# MCU_ZC-ST4X-A005A_1.net
KiCad netlist of a schematic drawn in Altium Designer
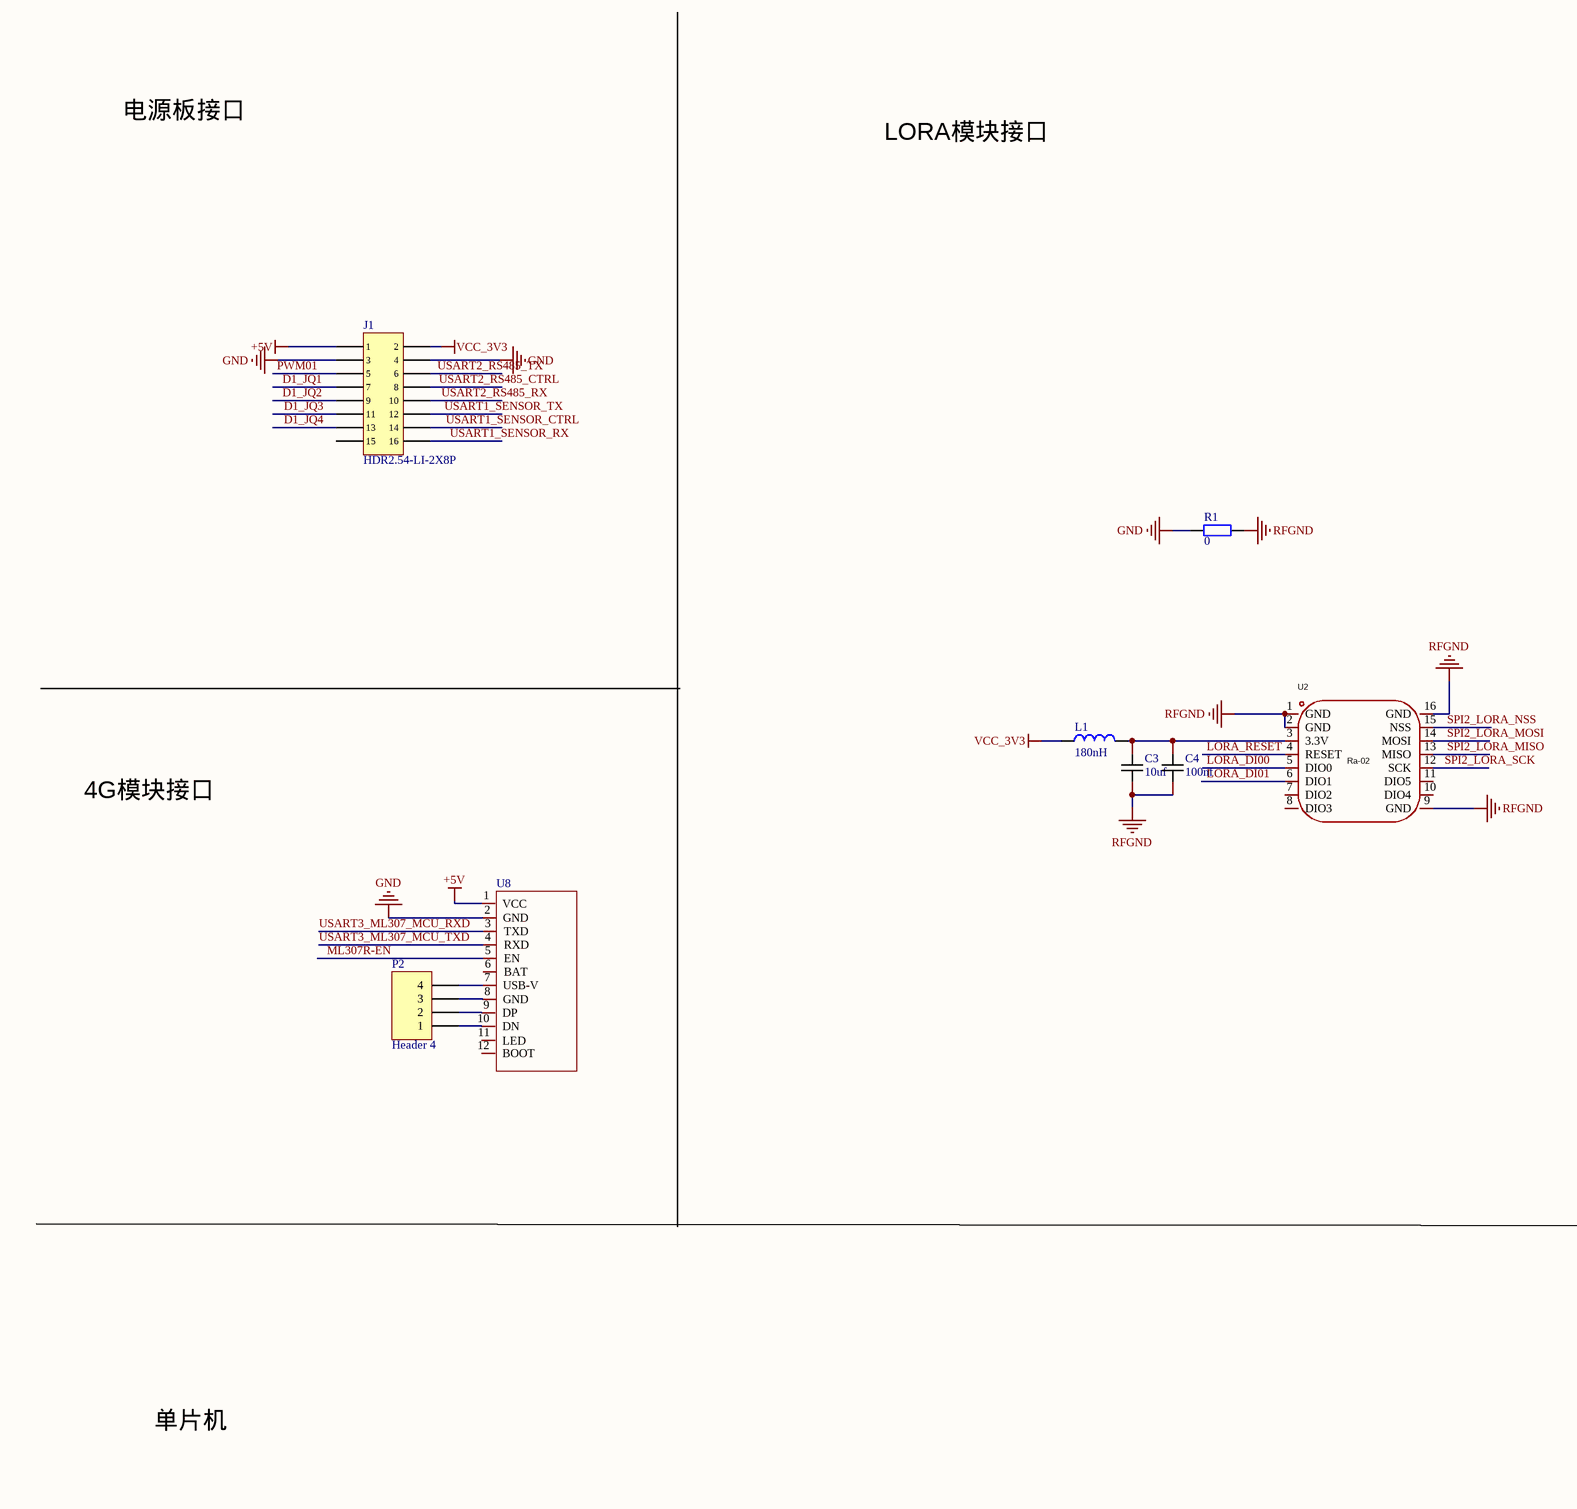
[diagram p0: MCU(ZC-ST4X-A005A)(1).SchDoc, top left]
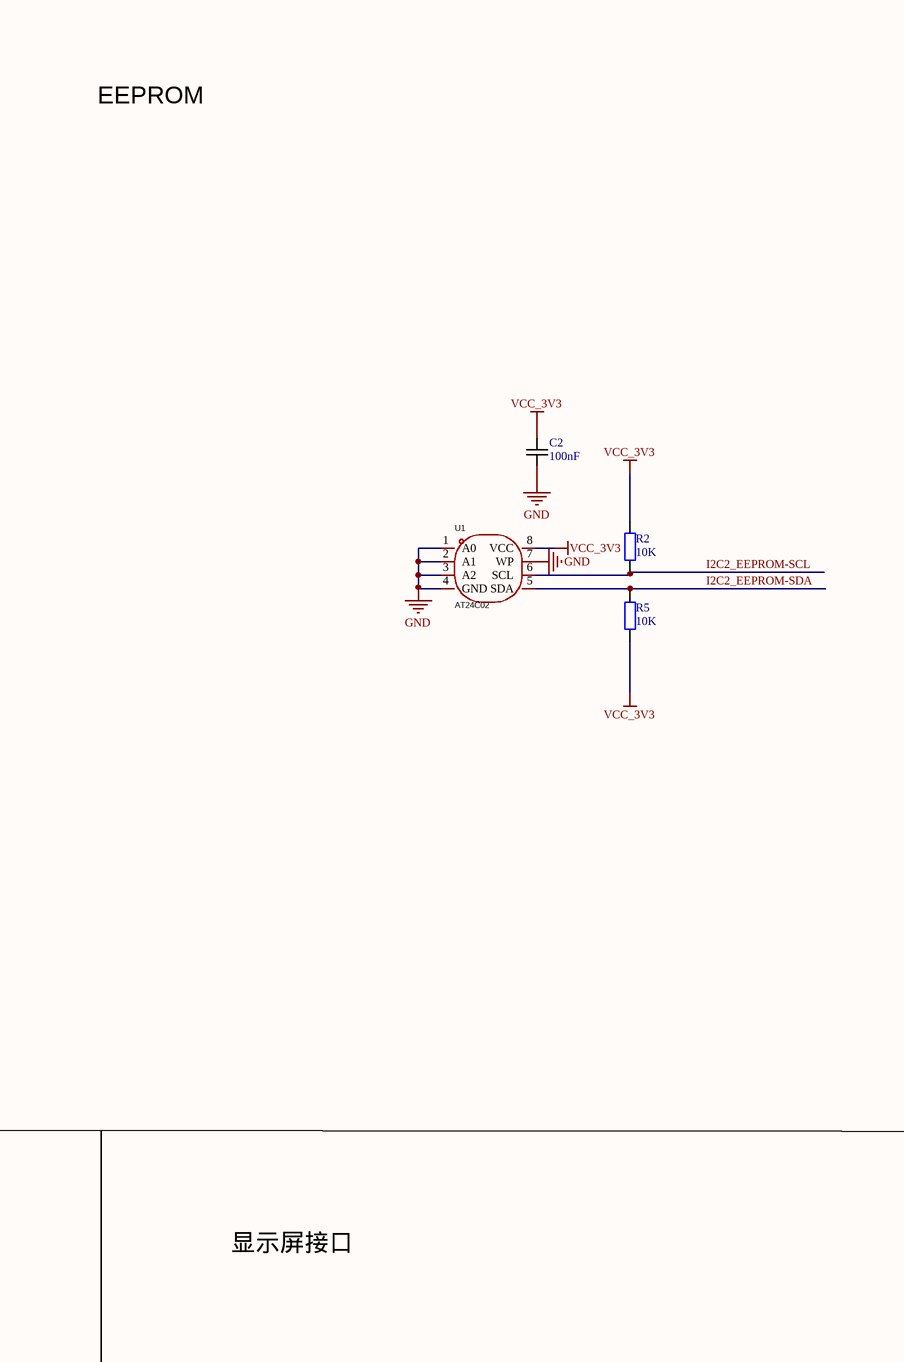
[diagram p1: MCU(ZC-ST4X-A005A)(1).SchDoc, top middle]
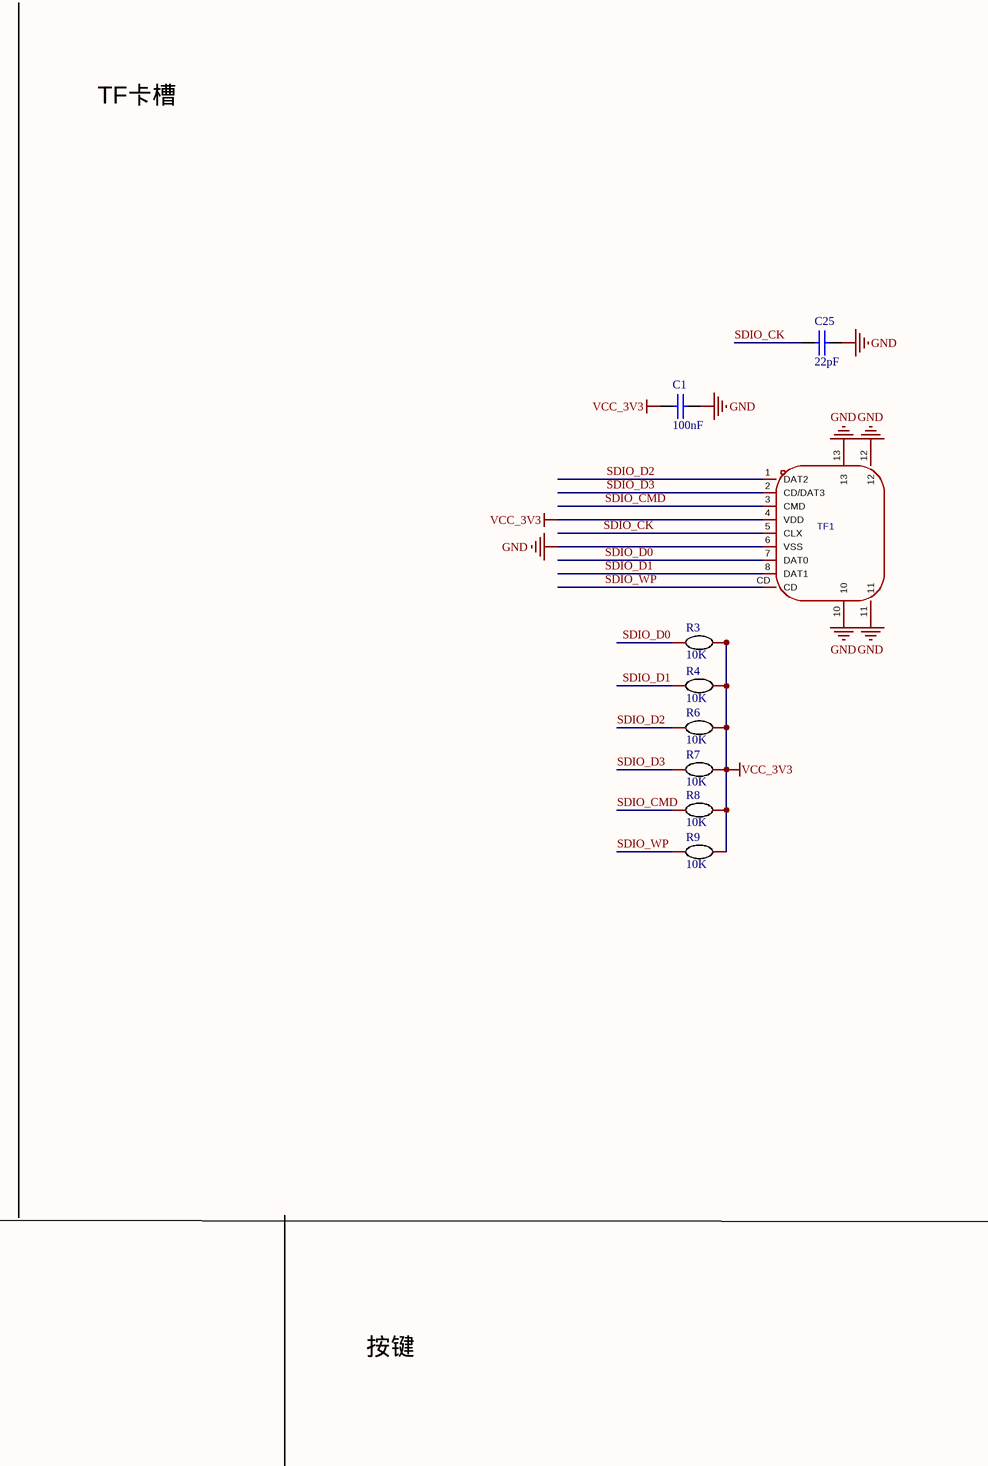
[diagram p2: MCU(ZC-ST4X-A005A)(1).SchDoc, top right]
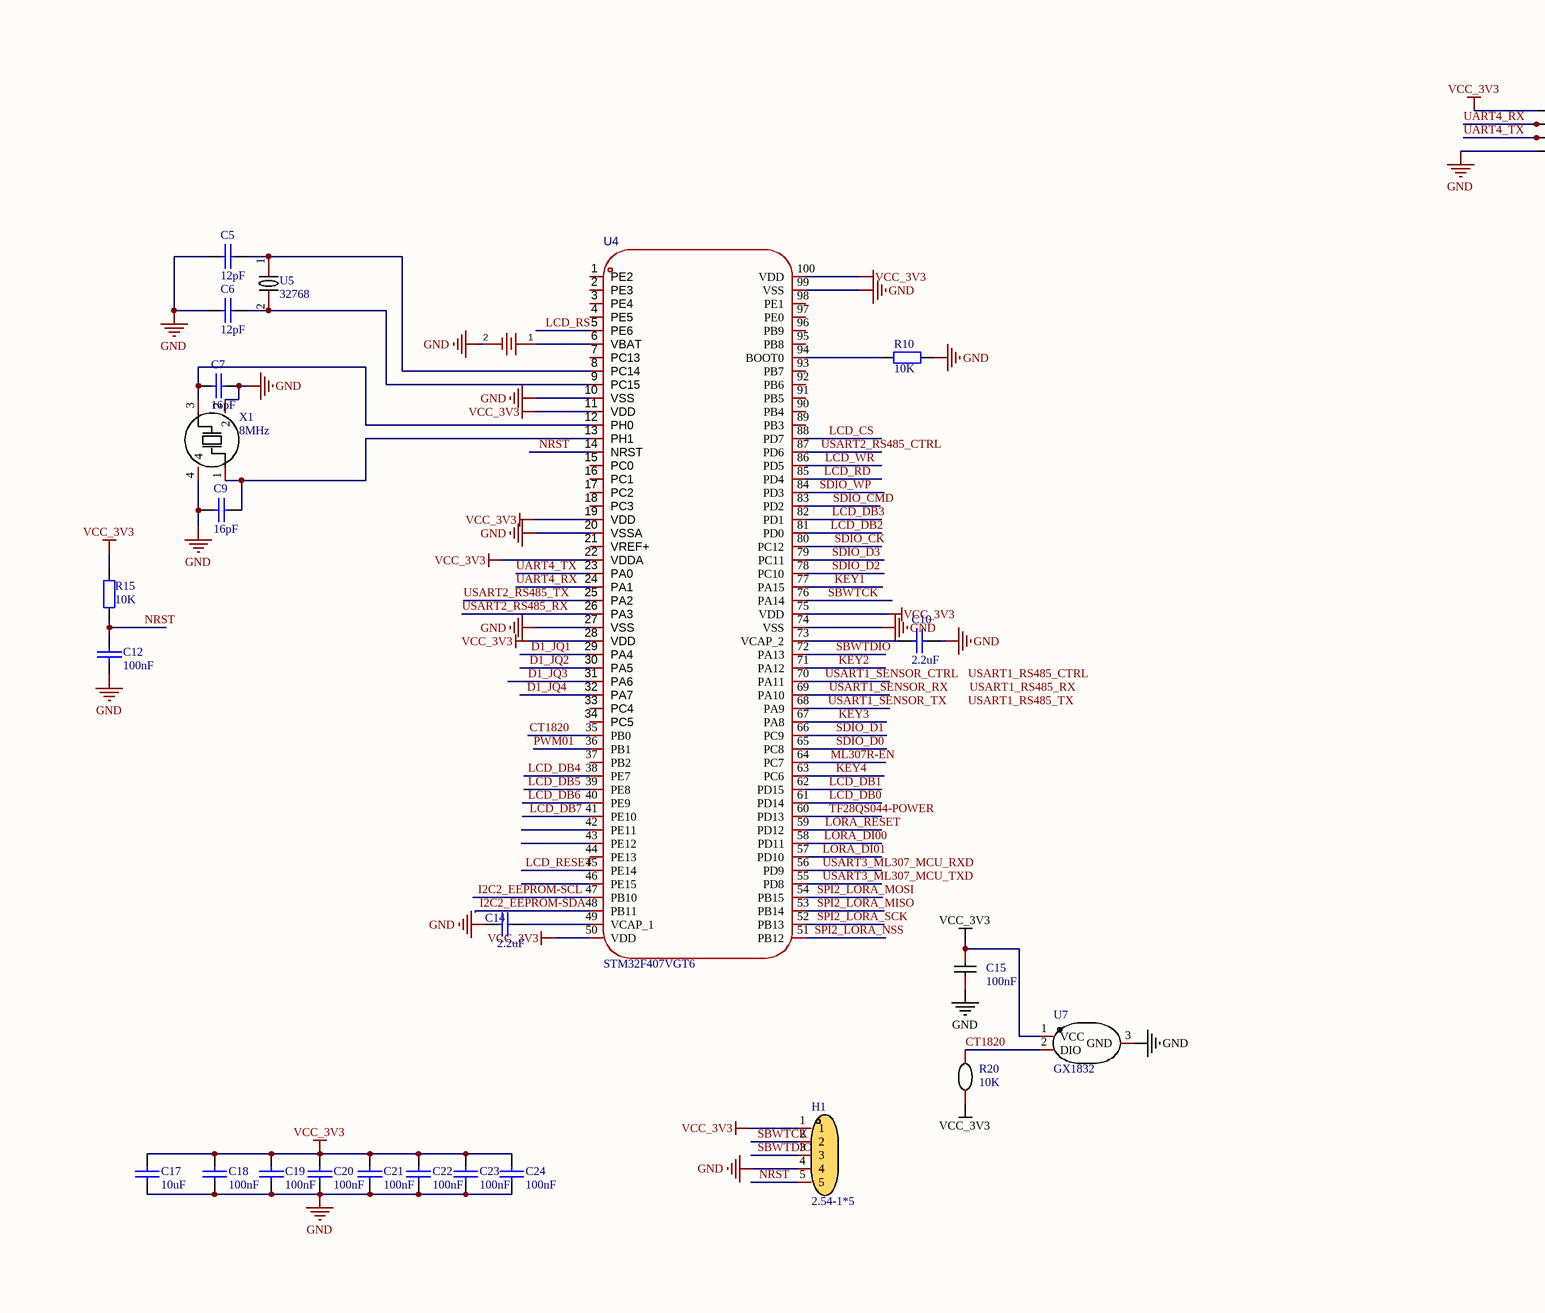
[diagram p3: MCU(ZC-ST4X-A005A)(1).SchDoc, bottom left]
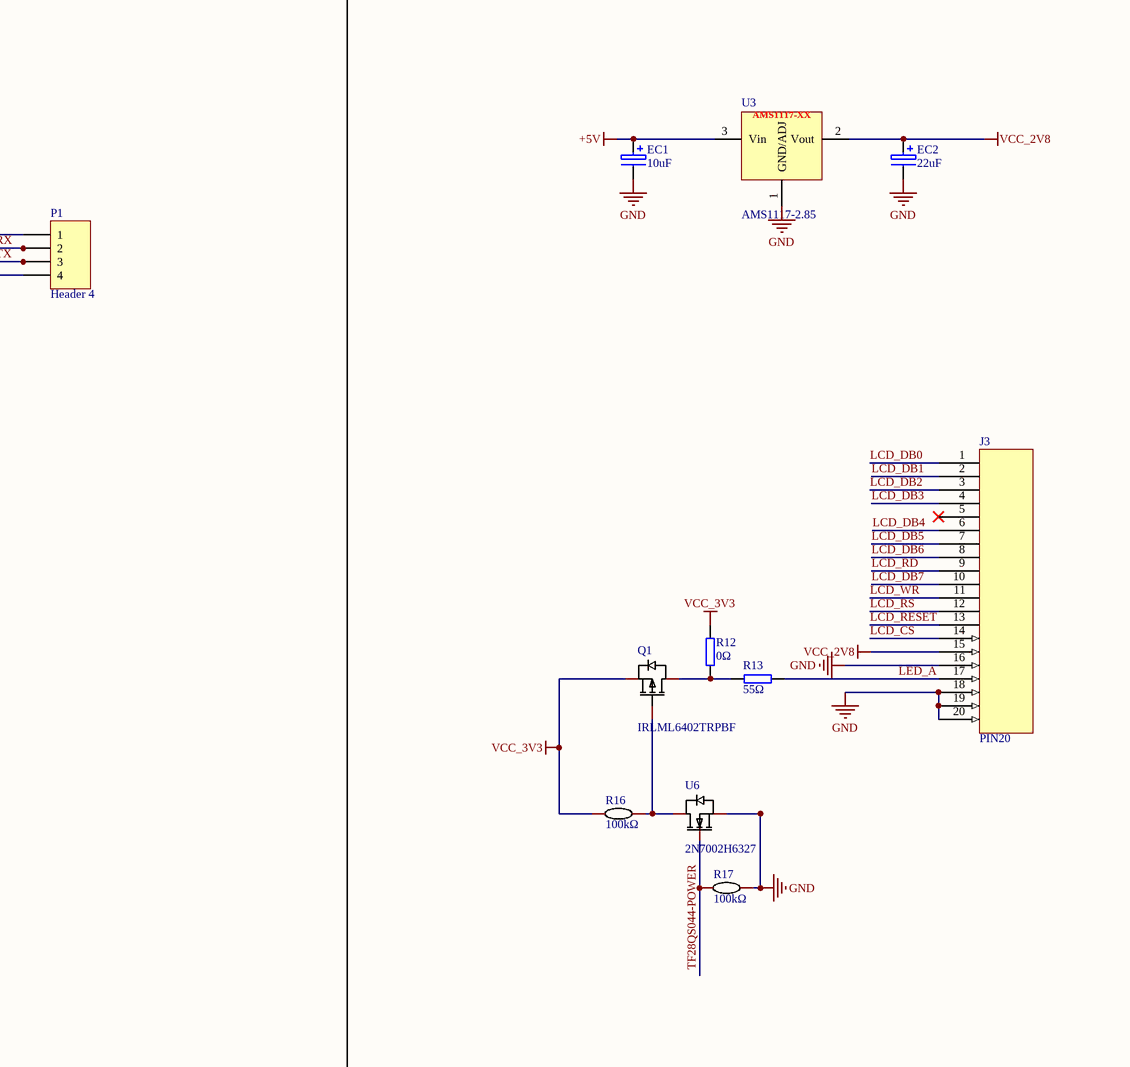
[diagram p4: MCU(ZC-ST4X-A005A)(1).SchDoc, bottom middle]
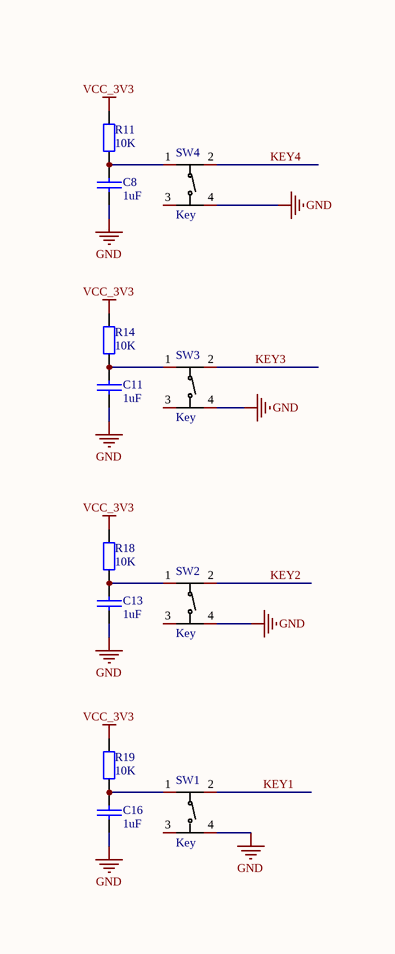
[diagram p5: MCU(ZC-ST4X-A005A)(1).SchDoc, bottom right]

(export (version "E")
  (design (tool "Eeschema 10.0.6"))
  (components
    (comp (ref "BAT1")
      (value "KH-CR2032-2-1")
      (footprint "BAT-TH_CR2032-BS-6-1")
      (libsource (lib "altium-import") (part "root_0_KH-CR2032-2-1_"))
    )
    (comp (ref "C1")
      (value "100nF")
      (footprint "C-0603")
      (description "电容")
      (libsource (lib "泰开常用器件") (part "C普通电容"))
    )
    (comp (ref "C2")
      (value "100nF")
      (footprint "C-0603")
      (fields
        (field (name "MANUFACTURER") "FH(风华)")
        (field (name "MANUFACTURER PART") "0805B104K500NT")
        (field (name "TOLERANCE") "±10%")
      )
      (libsource (lib "") (part "root_1_0805B104K500NT__1"))
    )
    (comp (ref "C3")
      (value "10uf")
      (footprint "C-0603")
      (fields
        (field (name "MANUFACTURER") "FH(风华)")
        (field (name "MANUFACTURER PART") "0805B104K500NT")
        (field (name "TOLERANCE") "±10%")
      )
      (libsource (lib "") (part "root_1_0805B104K500NT__1"))
    )
    (comp (ref "C4")
      (value "100nf")
      (footprint "C-0603")
      (fields
        (field (name "MANUFACTURER") "FH(风华)")
        (field (name "MANUFACTURER PART") "0805B104K500NT")
        (field (name "TOLERANCE") "±10%")
      )
      (libsource (lib "") (part "root_1_0805B104K500NT__1"))
    )
    (comp (ref "C5")
      (value "12pF")
      (footprint "C-0603")
      (description "电容")
      (libsource (lib "泰开常用器件") (part "C普通电容"))
    )
    (comp (ref "C6")
      (value "12pF")
      (footprint "C-0603")
      (description "电容")
      (libsource (lib "泰开常用器件") (part "C普通电容"))
    )
    (comp (ref "C7")
      (value "16pF")
      (footprint "C-0603")
      (description "电容")
      (libsource (lib "泰开常用器件") (part "C普通电容"))
    )
    (comp (ref "C8")
      (value "1uF")
      (footprint "C-0805")
      (description "电容")
      (libsource (lib "泰开常用器件") (part "C普通电容"))
    )
    (comp (ref "C9")
      (value "16pF")
      (footprint "C-0603")
      (description "电容")
      (libsource (lib "泰开常用器件") (part "C普通电容"))
    )
    (comp (ref "C10")
      (value "2.2uF")
      (footprint "C-0603")
      (description "电容")
      (libsource (lib "泰开常用器件") (part "C普通电容"))
    )
    (comp (ref "C11")
      (value "1uF")
      (footprint "C-0805")
      (description "电容")
      (libsource (lib "泰开常用器件") (part "C普通电容"))
    )
    (comp (ref "C12")
      (value "100nF")
      (footprint "C-0603")
      (description "电容")
      (libsource (lib "泰开常用器件") (part "C普通电容"))
    )
    (comp (ref "C13")
      (value "1uF")
      (footprint "C-0805")
      (description "电容")
      (libsource (lib "泰开常用器件") (part "C普通电容"))
    )
    (comp (ref "C14")
      (value "2.2uF")
      (footprint "C-0603")
      (description "电容")
      (libsource (lib "泰开常用器件") (part "C普通电容"))
    )
    (comp (ref "C15")
      (value "100nF")
      (footprint "C-0603")
      (fields
        (field (name "NAME") "100nF")
        (field (name "MANUFACTURER") "FH(风华)")
        (field (name "MANUFACTURER PART") "0805B104K500NT")
        (field (name "TOLERANCE") "±10%")
      )
      (libsource (lib "altium-import") (part "root_1_0805B104K500NT_"))
    )
    (comp (ref "C16")
      (value "1uF")
      (footprint "C-0805")
      (description "电容")
      (libsource (lib "泰开常用器件") (part "C普通电容"))
    )
    (comp (ref "C17")
      (value "10uF")
      (footprint "C-0603")
      (description "电容")
      (libsource (lib "泰开常用器件") (part "C普通电容"))
    )
    (comp (ref "C18")
      (value "100nF")
      (footprint "C-0603")
      (description "电容")
      (libsource (lib "泰开常用器件") (part "C普通电容"))
    )
    (comp (ref "C19")
      (value "100nF")
      (footprint "C-0603")
      (description "电容")
      (libsource (lib "泰开常用器件") (part "C普通电容"))
    )
    (comp (ref "C20")
      (value "100nF")
      (footprint "C-0603")
      (description "电容")
      (libsource (lib "泰开常用器件") (part "C普通电容"))
    )
    (comp (ref "C21")
      (value "100nF")
      (footprint "C-0603")
      (description "电容")
      (libsource (lib "泰开常用器件") (part "C普通电容"))
    )
    (comp (ref "C22")
      (value "100nF")
      (footprint "C-0603")
      (description "电容")
      (libsource (lib "泰开常用器件") (part "C普通电容"))
    )
    (comp (ref "C23")
      (value "100nF")
      (footprint "C-0603")
      (description "电容")
      (libsource (lib "泰开常用器件") (part "C普通电容"))
    )
    (comp (ref "C24")
      (value "100nF")
      (footprint "C-0603")
      (description "电容")
      (libsource (lib "泰开常用器件") (part "C普通电容"))
    )
    (comp (ref "C25")
      (value "22pF")
      (footprint "C-0603")
      (description "电容")
      (libsource (lib "泰开常用器件") (part "C普通电容"))
    )
    (comp (ref "EC1") (value "10uF") (footprint "C4*H") (libsource (lib "电容") (part "CAP-EC")))
    (comp (ref "EC2") (value "22uF") (footprint "C4*H") (libsource (lib "电容") (part "CAP-EC")))
    (comp (ref "H1")
      (value "2.54-1*5")
      (footprint "HDR-TH_5P-P2.54-V-M")
      (libsource (lib "泰开常用器件(3)") (part "2.54-1*5"))
    )
    (comp (ref "J1")
      (value "HDR2.54-LI-2X8P")
      (footprint "IDC-TH_16P-P2.54_BOOMELE-2X8P")
      (description "直插立式双排针")
      (libsource (lib "排针排母") (part "HDR2.54-LI-2X8P"))
    )
    (comp (ref "J3")
      (value "PIN20")
      (footprint "FPC-SMD_KH-CL0.5-H2.0-18PS")
      (libsource (lib "连接器") (part "PIN20"))
    )
    (comp (ref "L1")
      (value "180nH")
      (footprint "R-0805")
      (description "贴片电感")
      (libsource (lib "电感") (part "0603' 180nH 2% 0.24A 车规"))
    )
    (comp (ref "P1")
      (value "Header 4")
      (footprint "HDR2.54-M-LI-4P")
      (description "Header, 4-Pin")
      (fields (field (name "PUBLISHER") "Altium Limited"))
      (libsource (lib "") (part "Header 4_1"))
    )
    (comp (ref "P2")
      (value "Header 4")
      (footprint "HDR2.54-M-LI-4P")
      (description "Header, 4-Pin")
      (fields (field (name "PUBLISHER") "Altium Limited"))
      (libsource (lib "连接器") (part "Header 4"))
    )
    (comp (ref "Q1")
      (value "IRLML6402TRPBF")
      (footprint "SOT-23-3_L2.9-W1.6-P1.90-LS2.8-BR")
      (fields (field (name "NAME") "IRLML6402TRPBF") (field (name "MANUFACTURER") "Infineon(英飞凌)"))
      (libsource (lib "altium-import") (part "root_1_mirrored_IRLML6402TRPBF_C2593_"))
    )
    (comp (ref "R1")
      (value "0")
      (footprint "R-0805")
      (description "贴片电阻，未编号，未录入华芯元件库，临时封装，包括0201，0402，0603，0805，1206，1210，1812，2010，2512")
      (libsource (lib "") (part "通用电阻_1"))
    )
    (comp (ref "R2")
      (value "10K")
      (footprint "R-0603")
      (description "贴片电阻，未编号，未录入华芯元件库，临时封装，包括0201，0402，0603，0805，1206，1210，1812，2010，2512")
      (libsource (lib "电阻") (part "通用电阻"))
    )
    (comp (ref "R3")
      (value "TPM2S103P110R")
      (footprint "R-0603")
      (fields (field (name "NAME") "10K"))
      (libsource (lib "altium-import") (part "root_0_TPM2S103P110R_"))
    )
    (comp (ref "R4")
      (value "TPM2S103P110R")
      (footprint "R-0603")
      (fields (field (name "NAME") "10K"))
      (libsource (lib "altium-import") (part "root_0_TPM2S103P110R_"))
    )
    (comp (ref "R5")
      (value "10K")
      (footprint "R-0603")
      (description "贴片电阻，未编号，未录入华芯元件库，临时封装，包括0201，0402，0603，0805，1206，1210，1812，2010，2512")
      (libsource (lib "电阻") (part "通用电阻"))
    )
    (comp (ref "R6")
      (value "TPM2S103P110R")
      (footprint "R-0603")
      (fields (field (name "NAME") "10K"))
      (libsource (lib "altium-import") (part "root_0_TPM2S103P110R_"))
    )
    (comp (ref "R7")
      (value "TPM2S103P110R")
      (footprint "R-0603")
      (fields (field (name "NAME") "10K"))
      (libsource (lib "altium-import") (part "root_0_TPM2S103P110R_"))
    )
    (comp (ref "R8")
      (value "TPM2S103P110R")
      (footprint "R-0603")
      (fields (field (name "NAME") "10K"))
      (libsource (lib "altium-import") (part "root_0_TPM2S103P110R_"))
    )
    (comp (ref "R9")
      (value "TPM2S103P110R")
      (footprint "R-0603")
      (fields (field (name "NAME") "10K"))
      (libsource (lib "altium-import") (part "root_0_TPM2S103P110R_"))
    )
    (comp (ref "R10")
      (value "10K")
      (footprint "R-0603")
      (description "电阻")
      (fields (field (name "PUBLISHER") "Altium Limited"))
      (libsource (lib "泰开常用器件") (part "RES"))
    )
    (comp (ref "R11")
      (value "10K")
      (footprint "R-0805")
      (description "电阻")
      (fields (field (name "PUBLISHER") "Altium Limited"))
      (libsource (lib "") (part "RES_1"))
    )
    (comp (ref "R12")
      (value "0Ω")
      (footprint "R-0805")
      (description "0603")
      (libsource (lib "电阻  电位器") (part "RES-SMD"))
    )
    (comp (ref "R13")
      (value "55Ω")
      (footprint "R-0805")
      (description "0603")
      (libsource (lib "电阻  电位器") (part "RES-SMD"))
    )
    (comp (ref "R14")
      (value "10K")
      (footprint "R-0805")
      (description "电阻")
      (fields (field (name "PUBLISHER") "Altium Limited"))
      (libsource (lib "") (part "RES_1"))
    )
    (comp (ref "R15")
      (value "10K")
      (footprint "C-0603")
      (description "电阻")
      (fields (field (name "PUBLISHER") "Altium Limited"))
      (libsource (lib "") (part "RES_1"))
    )
    (comp (ref "R16")
      (value "100kΩ")
      (footprint "r0805")
      (description "电阻类型:厚膜电阻;阻值:10kΩ;精度:±1%;功率:125mW;温度系数:±100ppm/℃;最大工作电压:150V;工作温度范围:-55℃~+155℃;")
      (fields
        (field (name "NAME") "100kΩ")
        (field (name "MANUFACTURER") "UNI-ROYAL(厚声)")
        (field (name "MANUFACTURER PART") "0805W8F1002T5E")
      )
      (libsource (lib "altium-import") (part "root_2_0805W8F1002T5E_C17414_"))
    )
    (comp (ref "R17")
      (value "100kΩ")
      (footprint "r0805")
      (description "电阻类型:厚膜电阻;阻值:10kΩ;精度:±1%;功率:125mW;温度系数:±100ppm/℃;最大工作电压:150V;工作温度范围:-55℃~+155℃;")
      (fields
        (field (name "NAME") "100kΩ")
        (field (name "MANUFACTURER") "UNI-ROYAL(厚声)")
        (field (name "MANUFACTURER PART") "0805W8F1002T5E")
      )
      (libsource (lib "altium-import") (part "root_2_0805W8F1002T5E_C17414_"))
    )
    (comp (ref "R18")
      (value "10K")
      (footprint "R-0805")
      (description "电阻")
      (fields (field (name "PUBLISHER") "Altium Limited"))
      (libsource (lib "") (part "RES_1"))
    )
    (comp (ref "R19")
      (value "10K")
      (footprint "R-0805")
      (description "电阻")
      (fields (field (name "PUBLISHER") "Altium Limited"))
      (libsource (lib "") (part "RES_1"))
    )
    (comp (ref "R20")
      (value "TPM2S103P110R")
      (footprint "R-0603")
      (fields (field (name "NAME") "10K"))
      (libsource (lib "altium-import") (part "root_1_TPM2S103P110R_"))
    )
    (comp (ref "SW1") (value "Key") (footprint "12X12轻触按键") (libsource (lib "泰开常用器件") (part "Key")))
    (comp (ref "SW2") (value "Key") (footprint "12X12轻触按键") (libsource (lib "泰开常用器件") (part "Key")))
    (comp (ref "SW3") (value "Key") (footprint "12X12轻触按键") (libsource (lib "泰开常用器件") (part "Key")))
    (comp (ref "SW4") (value "Key") (footprint "12X12轻触按键") (libsource (lib "泰开常用器件") (part "Key")))
    (comp (ref "TF1")
      (value "TF-012")
      (footprint "TF-SMD_TF-012")
      (libsource (lib "altium-import") (part "root_0_TF-012_"))
    )
    (comp (ref "U1")
      (value "AT24C02")
      (footprint "SOIC-8")
      (fields (field (name "MANUFACTURER") "IDCHIP(英锐芯)"))
      (libsource (lib "altium-import") (part "root_0_AT24C02_C688857_"))
    )
    (comp (ref "U2")
      (value "Ra-02")
      (footprint "WIRELM-SMD_RA-02-BL")
      (fields (field (name "MANUFACTURER") "Ai-Thinker(安信可)"))
      (libsource (lib "altium-import") (part "root_0_Ra-02_C90039_"))
    )
    (comp (ref "U3")
      (value "AMS1117-2.85")
      (footprint "SOT-223-4")
      (description "AMS   800mA LOW DROPOUT VOLTAGE REGULATOR")
      (libsource (lib "电源管理") (part "AMS1117-XX"))
    )
    (comp (ref "U4")
      (value "STM32F407VGT6")
      (footprint "LQFP-100_L14.0-W14.0-P0.50-LS16.0-BL")
      (libsource (lib "单片机") (part "STM32F407VGT6"))
    )
    (comp (ref "U5")
      (value "32768")
      (footprint "CRYSTAL-SMD_L3.2-W1.5")
      (libsource (lib "泰开常用器件") (part "7N032768NW2"))
    )
    (comp (ref "U6")
      (value "2N7002H6327")
      (footprint "PG-SOT23-3_L2.9-W1.3-P1.90-LS2.4-BR")
      (fields (field (name "NAME") "2N7002H6327") (field (name "MANUFACTURER") "Infineon(英飞凌)"))
      (libsource (lib "altium-import") (part "root_1_2N7002 H6327_"))
    )
    (comp (ref "U7")
      (value "CT1720KR")
      (footprint "SOT-23-3")
      (fields (field (name "NAME") "GX1832") (field (name "MANUFACTURER") "SENSYLINK(申矽凌)"))
      (libsource (lib "altium-import") (part "root_0_CT1720KR_"))
    )
    (comp (ref "U8") (value "U8") (footprint "4G") (libsource (lib "模块") (part "4G(ML307R)")))
    (comp (ref "X1")
      (value "8MHz")
      (footprint "CRYSTAL-SMD_4P-L3.2-W2.5-BL")
      (libsource (lib "泰开常用器件") (part "无源晶振"))
    )
  )
  (nets
    (net (code "1") (name "+5V") (class "Default")
      (node (ref "EC1") (pin "1") (pinfunction "1_1") (pintype "passive"))
      (node (ref "J1") (pin "1") (pinfunction "1_1") (pintype "passive"))
      (node (ref "U3") (pin "3") (pinfunction "Vin_3") (pintype "passive"))
      (node (ref "U8") (pin "1") (pinfunction "VCC_1") (pintype "passive"))
    )
    (net (code "2") (name "/CT1820") (class "Default")
      (node (ref "R20") (pin "2") (pinfunction "2_2") (pintype "passive"))
      (node (ref "U4") (pin "35") (pinfunction "PB0_35") (pintype "passive"))
      (node (ref "U7") (pin "2") (pinfunction "DIO_2") (pintype "passive"))
    )
    (net (code "3") (name "/D1_JQ1") (class "Default")
      (node (ref "J1") (pin "7") (pinfunction "7_7") (pintype "passive"))
      (node (ref "U4") (pin "29") (pinfunction "PA4_29") (pintype "passive"))
    )
    (net (code "4") (name "/D1_JQ2") (class "Default")
      (node (ref "J1") (pin "9") (pinfunction "9_9") (pintype "passive"))
      (node (ref "U4") (pin "30") (pinfunction "PA5_30") (pintype "passive"))
    )
    (net (code "5") (name "/D1_JQ3") (class "Default")
      (node (ref "J1") (pin "11") (pinfunction "11_11") (pintype "passive"))
      (node (ref "U4") (pin "31") (pinfunction "PA6_31") (pintype "passive"))
    )
    (net (code "6") (name "/D1_JQ4") (class "Default")
      (node (ref "J1") (pin "13") (pinfunction "13_13") (pintype "passive"))
      (node (ref "U4") (pin "32") (pinfunction "PA7_32") (pintype "passive"))
    )
    (net (code "7") (name "/I2C2_EEPROM-SCL") (class "Default")
      (node (ref "R2") (pin "1") (pinfunction "1_1") (pintype "passive"))
      (node (ref "U1") (pin "6") (pinfunction "SCL_6") (pintype "passive"))
      (node (ref "U4") (pin "47") (pinfunction "PB10_47") (pintype "passive"))
    )
    (net (code "8") (name "/I2C2_EEPROM-SDA") (class "Default")
      (node (ref "R5") (pin "2") (pinfunction "2_2") (pintype "passive"))
      (node (ref "U1") (pin "5") (pinfunction "SDA_5") (pintype "passive"))
      (node (ref "U4") (pin "48") (pinfunction "PB11_48") (pintype "passive"))
    )
    (net (code "9") (name "/KEY1") (class "Default")
      (node (ref "SW1") (pin "2") (pinfunction "2_2") (pintype "passive"))
      (node (ref "U4") (pin "77") (pinfunction "PA15_77") (pintype "passive"))
    )
    (net (code "10") (name "/KEY2") (class "Default")
      (node (ref "SW2") (pin "2") (pinfunction "2_2") (pintype "passive"))
      (node (ref "U4") (pin "71") (pinfunction "PA12_71") (pintype "passive"))
    )
    (net (code "11") (name "/KEY3") (class "Default")
      (node (ref "SW3") (pin "2") (pinfunction "2_2") (pintype "passive"))
      (node (ref "U4") (pin "67") (pinfunction "PA8_67") (pintype "passive"))
    )
    (net (code "12") (name "/KEY4") (class "Default")
      (node (ref "SW4") (pin "2") (pinfunction "2_2") (pintype "passive"))
      (node (ref "U4") (pin "63") (pinfunction "PC6_63") (pintype "passive"))
    )
    (net (code "13") (name "/LCD_CS") (class "Default")
      (node (ref "J3") (pin "14") (pinfunction "14_14") (pintype "input"))
      (node (ref "U4") (pin "88") (pinfunction "PD7_88") (pintype "passive"))
    )
    (net (code "14") (name "/LCD_DB0") (class "Default")
      (node (ref "J3") (pin "1") (pintype "passive"))
      (node (ref "U4") (pin "61") (pinfunction "PD14_61") (pintype "passive"))
    )
    (net (code "15") (name "/LCD_DB1") (class "Default")
      (node (ref "J3") (pin "2") (pintype "passive"))
      (node (ref "U4") (pin "62") (pinfunction "PD15_62") (pintype "passive"))
    )
    (net (code "16") (name "/LCD_DB2") (class "Default")
      (node (ref "J3") (pin "3") (pintype "passive"))
      (node (ref "U4") (pin "81") (pinfunction "PD0_81") (pintype "passive"))
    )
    (net (code "17") (name "/LCD_DB3") (class "Default")
      (node (ref "J3") (pin "4") (pintype "passive"))
      (node (ref "U4") (pin "82") (pinfunction "PD1_82") (pintype "passive"))
    )
    (net (code "18") (name "/LCD_DB4") (class "Default")
      (node (ref "J3") (pin "6") (pintype "passive"))
      (node (ref "U4") (pin "38") (pinfunction "PE7_38") (pintype "passive"))
    )
    (net (code "19") (name "/LCD_DB5") (class "Default")
      (node (ref "J3") (pin "7") (pintype "passive"))
      (node (ref "U4") (pin "39") (pinfunction "PE8_39") (pintype "passive"))
    )
    (net (code "20") (name "/LCD_DB6") (class "Default")
      (node (ref "J3") (pin "8") (pintype "passive"))
      (node (ref "U4") (pin "40") (pinfunction "PE9_40") (pintype "passive"))
    )
    (net (code "21") (name "/LCD_DB7") (class "Default")
      (node (ref "J3") (pin "10") (pintype "passive"))
      (node (ref "U4") (pin "41") (pinfunction "PE10_41") (pintype "passive"))
    )
    (net (code "22") (name "/LCD_RD") (class "Default")
      (node (ref "J3") (pin "9") (pintype "passive"))
      (node (ref "U4") (pin "85") (pinfunction "PD4_85") (pintype "passive"))
    )
    (net (code "23") (name "/LCD_RESET") (class "Default")
      (node (ref "J3") (pin "13") (pinfunction "13_13") (pintype "passive"))
      (node (ref "U4") (pin "45") (pinfunction "PE14_45") (pintype "passive"))
    )
    (net (code "24") (name "/LCD_RS") (class "Default")
      (node (ref "J3") (pin "12") (pinfunction "12_12") (pintype "passive"))
      (node (ref "U4") (pin "5") (pinfunction "PE6_5") (pintype "passive"))
    )
    (net (code "25") (name "/LCD_WR") (class "Default")
      (node (ref "J3") (pin "11") (pinfunction "11_11") (pintype "passive"))
      (node (ref "U4") (pin "86") (pinfunction "PD5_86") (pintype "passive"))
    )
    (net (code "26") (name "/LED_A") (class "Default")
      (node (ref "J3") (pin "17") (pinfunction "17_17") (pintype "input"))
      (node (ref "R13") (pin "1") (pinfunction "1_1") (pintype "passive"))
    )
    (net (code "27") (name "/LORA_DI00") (class "Default")
      (node (ref "U2") (pin "5") (pinfunction "DIO0_5") (pintype "passive"))
      (node (ref "U4") (pin "58") (pinfunction "PD11_58") (pintype "passive"))
    )
    (net (code "28") (name "/LORA_DI01") (class "Default")
      (node (ref "U2") (pin "6") (pinfunction "DIO1_6") (pintype "passive"))
      (node (ref "U4") (pin "57") (pinfunction "PD10_57") (pintype "passive"))
    )
    (net (code "29") (name "/LORA_RESET") (class "Default")
      (node (ref "U2") (pin "4") (pinfunction "RESET_4") (pintype "passive"))
      (node (ref "U4") (pin "59") (pinfunction "PD12_59") (pintype "passive"))
    )
    (net (code "30") (name "/ML307R-EN") (class "Default")
      (node (ref "U4") (pin "64") (pinfunction "PC7_64") (pintype "passive"))
      (node (ref "U8") (pin "5") (pinfunction "EN_5") (pintype "passive"))
    )
    (net (code "31") (name "/NRST") (class "Default")
      (node (ref "C12") (pin "2") (pinfunction "2_2") (pintype "passive"))
      (node (ref "H1") (pin "5") (pinfunction "5_5") (pintype "passive"))
      (node (ref "R15") (pin "1") (pinfunction "1_1") (pintype "passive"))
      (node (ref "U4") (pin "14") (pinfunction "NRST_14") (pintype "passive"))
    )
    (net (code "32") (name "/PWM01") (class "Default")
      (node (ref "J1") (pin "5") (pinfunction "5_5") (pintype "passive"))
      (node (ref "U4") (pin "36") (pinfunction "PB1_36") (pintype "passive"))
    )
    (net (code "33") (name "/SBWTCK") (class "Default")
      (node (ref "H1") (pin "2") (pinfunction "2_2") (pintype "passive"))
      (node (ref "U4") (pin "76") (pinfunction "PA14_76") (pintype "passive"))
    )
    (net (code "34") (name "/SBWTDIO") (class "Default")
      (node (ref "H1") (pin "3") (pinfunction "3_3") (pintype "passive"))
      (node (ref "U4") (pin "72") (pinfunction "PA13_72") (pintype "passive"))
    )
    (net (code "35") (name "/SDIO_CK") (class "Default")
      (node (ref "C25") (pin "1") (pinfunction "1_1") (pintype "passive"))
      (node (ref "TF1") (pin "5") (pinfunction "CLX_5") (pintype "passive"))
      (node (ref "U4") (pin "80") (pinfunction "PC12_80") (pintype "passive"))
    )
    (net (code "36") (name "/SDIO_CMD") (class "Default")
      (node (ref "R8") (pin "1") (pinfunction "1_1") (pintype "passive"))
      (node (ref "TF1") (pin "3") (pinfunction "CMD_3") (pintype "passive"))
      (node (ref "U4") (pin "83") (pinfunction "PD2_83") (pintype "passive"))
    )
    (net (code "37") (name "/SDIO_D0") (class "Default")
      (node (ref "R3") (pin "1") (pinfunction "1_1") (pintype "passive"))
      (node (ref "TF1") (pin "7") (pinfunction "DAT0_7") (pintype "passive"))
      (node (ref "U4") (pin "65") (pinfunction "PC8_65") (pintype "passive"))
    )
    (net (code "38") (name "/SDIO_D1") (class "Default")
      (node (ref "R4") (pin "1") (pinfunction "1_1") (pintype "passive"))
      (node (ref "TF1") (pin "8") (pinfunction "DAT1_8") (pintype "passive"))
      (node (ref "U4") (pin "66") (pinfunction "PC9_66") (pintype "passive"))
    )
    (net (code "39") (name "/SDIO_D2") (class "Default")
      (node (ref "R6") (pin "1") (pinfunction "1_1") (pintype "passive"))
      (node (ref "TF1") (pin "1") (pinfunction "DAT2_1") (pintype "passive"))
      (node (ref "U4") (pin "78") (pinfunction "PC10_78") (pintype "passive"))
    )
    (net (code "40") (name "/SDIO_D3") (class "Default")
      (node (ref "R7") (pin "1") (pinfunction "1_1") (pintype "passive"))
      (node (ref "TF1") (pin "2") (pinfunction "CD/DAT3_2") (pintype "passive"))
      (node (ref "U4") (pin "79") (pinfunction "PC11_79") (pintype "passive"))
    )
    (net (code "41") (name "/SDIO_WP") (class "Default")
      (node (ref "R9") (pin "1") (pinfunction "1_1") (pintype "passive"))
      (node (ref "TF1") (pin "CD") (pinfunction "CD_CD") (pintype "passive"))
      (node (ref "U4") (pin "84") (pinfunction "PD3_84") (pintype "passive"))
    )
    (net (code "42") (name "/SPI2_LORA_MISO") (class "Default")
      (node (ref "U2") (pin "13") (pinfunction "MISO_13") (pintype "passive"))
      (node (ref "U4") (pin "53") (pinfunction "PB14_53") (pintype "passive"))
    )
    (net (code "43") (name "/SPI2_LORA_MOSI") (class "Default")
      (node (ref "U2") (pin "14") (pinfunction "MOSI_14") (pintype "passive"))
      (node (ref "U4") (pin "54") (pinfunction "PB15_54") (pintype "passive"))
    )
    (net (code "44") (name "/SPI2_LORA_NSS") (class "Default")
      (node (ref "U2") (pin "15") (pinfunction "NSS_15") (pintype "passive"))
      (node (ref "U4") (pin "51") (pinfunction "PB12_51") (pintype "passive"))
    )
    (net (code "45") (name "/SPI2_LORA_SCK") (class "Default")
      (node (ref "U2") (pin "12") (pinfunction "SCK_12") (pintype "passive"))
      (node (ref "U4") (pin "52") (pinfunction "PB13_52") (pintype "passive"))
    )
    (net (code "46") (name "/TF28QS044-POWER") (class "Default")
      (node (ref "R17") (pin "2") (pinfunction "2_2") (pintype "passive"))
      (node (ref "U4") (pin "60") (pinfunction "PD13_60") (pintype "passive"))
      (node (ref "U6") (pin "1") (pinfunction "G_1") (pintype "passive"))
    )
    (net (code "47") (name "/UART4_RX") (class "Default")
      (node (ref "P1") (pin "2") (pinfunction "2_2") (pintype "passive"))
      (node (ref "U4") (pin "24") (pinfunction "PA1_24") (pintype "passive"))
    )
    (net (code "48") (name "/UART4_TX") (class "Default")
      (node (ref "P1") (pin "3") (pinfunction "3_3") (pintype "passive"))
      (node (ref "U4") (pin "23") (pinfunction "PA0_23") (pintype "passive"))
    )
    (net (code "52") (name "/USART1_SENSOR_CTRL") (class "Default")
      (node (ref "J1") (pin "14") (pinfunction "14_14") (pintype "passive"))
      (node (ref "U4") (pin "70") (pinfunction "PA11_70") (pintype "passive"))
    )
    (net (code "53") (name "/USART1_SENSOR_RX") (class "Default")
      (node (ref "J1") (pin "16") (pinfunction "16_16") (pintype "passive"))
      (node (ref "U4") (pin "69") (pinfunction "PA10_69") (pintype "passive"))
    )
    (net (code "54") (name "/USART1_SENSOR_TX") (class "Default")
      (node (ref "J1") (pin "12") (pinfunction "12_12") (pintype "passive"))
      (node (ref "U4") (pin "68") (pinfunction "PA9_68") (pintype "passive"))
    )
    (net (code "55") (name "/USART2_RS485_CTRL") (class "Default")
      (node (ref "J1") (pin "8") (pinfunction "8_8") (pintype "passive"))
      (node (ref "U4") (pin "87") (pinfunction "PD6_87") (pintype "passive"))
    )
    (net (code "56") (name "/USART2_RS485_RX") (class "Default")
      (node (ref "J1") (pin "10") (pinfunction "10_10") (pintype "passive"))
      (node (ref "U4") (pin "26") (pinfunction "PA3_26") (pintype "passive"))
    )
    (net (code "57") (name "/USART2_RS485_TX") (class "Default")
      (node (ref "J1") (pin "6") (pinfunction "6_6") (pintype "passive"))
      (node (ref "U4") (pin "25") (pinfunction "PA2_25") (pintype "passive"))
    )
    (net (code "58") (name "/USART3_ML307_MCU_RXD") (class "Default")
      (node (ref "U4") (pin "56") (pinfunction "PD9_56") (pintype "passive"))
      (node (ref "U8") (pin "3") (pinfunction "TXD_3") (pintype "passive"))
    )
    (net (code "59") (name "/USART3_ML307_MCU_TXD") (class "Default")
      (node (ref "U4") (pin "55") (pinfunction "PD8_55") (pintype "passive"))
      (node (ref "U8") (pin "4") (pinfunction "RXD_4") (pintype "passive"))
    )
    (net (code "60") (name "GND") (class "Default")
      (node (ref "BAT1") (pin "2") (pinfunction "2_2") (pintype "passive"))
      (node (ref "C1") (pin "1") (pinfunction "1_1") (pintype "passive"))
      (node (ref "C10") (pin "1") (pinfunction "1_1") (pintype "passive"))
      (node (ref "C11") (pin "1") (pinfunction "1_1") (pintype "passive"))
      (node (ref "C12") (pin "1") (pinfunction "1_1") (pintype "passive"))
      (node (ref "C13") (pin "1") (pinfunction "1_1") (pintype "passive"))
      (node (ref "C14") (pin "1") (pinfunction "1_1") (pintype "passive"))
      (node (ref "C15") (pin "1") (pinfunction "1_1") (pintype "passive"))
      (node (ref "C16") (pin "1") (pinfunction "1_1") (pintype "passive"))
      (node (ref "C17") (pin "1") (pinfunction "1_1") (pintype "passive"))
      (node (ref "C18") (pin "1") (pinfunction "1_1") (pintype "passive"))
      (node (ref "C19") (pin "1") (pinfunction "1_1") (pintype "passive"))
      (node (ref "C2") (pin "1") (pinfunction "1_1") (pintype "passive"))
      (node (ref "C20") (pin "1") (pinfunction "1_1") (pintype "passive"))
      (node (ref "C21") (pin "1") (pinfunction "1_1") (pintype "passive"))
      (node (ref "C22") (pin "1") (pinfunction "1_1") (pintype "passive"))
      (node (ref "C23") (pin "1") (pinfunction "1_1") (pintype "passive"))
      (node (ref "C24") (pin "1") (pinfunction "1_1") (pintype "passive"))
      (node (ref "C25") (pin "2") (pinfunction "2_2") (pintype "passive"))
      (node (ref "C5") (pin "1") (pinfunction "1_1") (pintype "passive"))
      (node (ref "C6") (pin "1") (pinfunction "1_1") (pintype "passive"))
      (node (ref "C7") (pin "1") (pinfunction "1_1") (pintype "passive"))
      (node (ref "C8") (pin "1") (pinfunction "1_1") (pintype "passive"))
      (node (ref "C9") (pin "2") (pinfunction "2_2") (pintype "passive"))
      (node (ref "EC1") (pin "2") (pinfunction "2_2") (pintype "passive"))
      (node (ref "EC2") (pin "2") (pinfunction "2_2") (pintype "passive"))
      (node (ref "H1") (pin "4") (pinfunction "4_4") (pintype "passive"))
      (node (ref "J1") (pin "3") (pinfunction "3_3") (pintype "passive"))
      (node (ref "J1") (pin "4") (pinfunction "4_4") (pintype "passive"))
      (node (ref "J3") (pin "16") (pinfunction "16_16") (pintype "input"))
      (node (ref "J3") (pin "18") (pinfunction "18_18") (pintype "input"))
      (node (ref "J3") (pin "19") (pinfunction "19_19") (pintype "input"))
      (node (ref "J3") (pin "20") (pinfunction "20_20") (pintype "input"))
      (node (ref "P1") (pin "4") (pinfunction "4_4") (pintype "passive"))
      (node (ref "R1") (pin "1") (pinfunction "1_1") (pintype "passive"))
      (node (ref "R10") (pin "1") (pinfunction "1_1") (pintype "passive"))
      (node (ref "R17") (pin "1") (pinfunction "1_1") (pintype "passive"))
      (node (ref "SW1") (pin "4") (pinfunction "4_4") (pintype "passive"))
      (node (ref "SW2") (pin "4") (pinfunction "4_4") (pintype "passive"))
      (node (ref "SW3") (pin "4") (pinfunction "4_4") (pintype "passive"))
      (node (ref "SW4") (pin "4") (pinfunction "4_4") (pintype "passive"))
      (node (ref "TF1") (pin "10") (pinfunction "10_10") (pintype "passive"))
      (node (ref "TF1") (pin "11") (pinfunction "11_11") (pintype "passive"))
      (node (ref "TF1") (pin "12") (pinfunction "12_12") (pintype "passive"))
      (node (ref "TF1") (pin "13") (pinfunction "13_13") (pintype "passive"))
      (node (ref "TF1") (pin "6") (pinfunction "VSS_6") (pintype "passive"))
      (node (ref "U1") (pin "1") (pinfunction "A0_1") (pintype "passive"))
      (node (ref "U1") (pin "2") (pinfunction "A1_2") (pintype "passive"))
      (node (ref "U1") (pin "3") (pinfunction "A2_3") (pintype "passive"))
      (node (ref "U1") (pin "4") (pinfunction "GND_4") (pintype "passive"))
      (node (ref "U1") (pin "7") (pinfunction "WP_7") (pintype "passive"))
      (node (ref "U3") (pin "1") (pinfunction "GND/ADJ_1") (pintype "passive"))
      (node (ref "U4") (pin "10") (pinfunction "VSS_10") (pintype "passive"))
      (node (ref "U4") (pin "20") (pinfunction "VSSA_20") (pintype "passive"))
      (node (ref "U4") (pin "27") (pinfunction "VSS_27") (pintype "passive"))
      (node (ref "U4") (pin "74") (pinfunction "VSS_74") (pintype "passive"))
      (node (ref "U4") (pin "99") (pinfunction "VSS_99") (pintype "passive"))
      (node (ref "U6") (pin "2") (pinfunction "S_2") (pintype "passive"))
      (node (ref "U7") (pin "3") (pinfunction "GND_3") (pintype "passive"))
      (node (ref "U8") (pin "2") (pinfunction "GND_2") (pintype "passive"))
      (node (ref "X1") (pin "2") (pinfunction "2_2") (pintype "passive"))
      (node (ref "X1") (pin "4") (pinfunction "4_4") (pintype "passive"))
    )
    (net (code "61") (name "Net-(C8-Pad2)") (class "Default")
      (node (ref "C8") (pin "2") (pinfunction "2_2") (pintype "passive"))
      (node (ref "R11") (pin "1") (pinfunction "1_1") (pintype "passive"))
      (node (ref "SW4") (pin "1") (pinfunction "1_1") (pintype "passive"))
    )
    (net (code "62") (name "Net-(C11-Pad2)") (class "Default")
      (node (ref "C11") (pin "2") (pinfunction "2_2") (pintype "passive"))
      (node (ref "R14") (pin "1") (pinfunction "1_1") (pintype "passive"))
      (node (ref "SW3") (pin "1") (pinfunction "1_1") (pintype "passive"))
    )
    (net (code "63") (name "Net-(C13-Pad2)") (class "Default")
      (node (ref "C13") (pin "2") (pinfunction "2_2") (pintype "passive"))
      (node (ref "R18") (pin "1") (pinfunction "1_1") (pintype "passive"))
      (node (ref "SW2") (pin "1") (pinfunction "1_1") (pintype "passive"))
    )
    (net (code "64") (name "Net-(C16-Pad2)") (class "Default")
      (node (ref "C16") (pin "2") (pinfunction "2_2") (pintype "passive"))
      (node (ref "R19") (pin "1") (pinfunction "1_1") (pintype "passive"))
      (node (ref "SW1") (pin "1") (pinfunction "1_1") (pintype "passive"))
    )
    (net (code "65") (name "Net-(P2-Pad3)") (class "Default")
      (node (ref "P2") (pin "3") (pinfunction "3_3") (pintype "passive"))
      (node (ref "U8") (pin "8") (pinfunction "GND_8") (pintype "passive"))
    )
    (net (code "66") (name "Net-(Q1-D)") (class "Default")
      (node (ref "Q1") (pin "3") (pinfunction "D_3") (pintype "passive"))
      (node (ref "R12") (pin "2") (pinfunction "2_2") (pintype "passive"))
      (node (ref "R13") (pin "2") (pinfunction "2_2") (pintype "passive"))
    )
    (net (code "67") (name "Net-(Q1-G)") (class "Default")
      (node (ref "Q1") (pin "1") (pinfunction "G_1") (pintype "passive"))
      (node (ref "R16") (pin "1") (pinfunction "1_1") (pintype "passive"))
      (node (ref "U6") (pin "3") (pinfunction "D_3") (pintype "passive"))
    )
    (net (code "68") (name "Net-(U2-3.3V)") (class "Default")
      (node (ref "C3") (pin "2") (pinfunction "2_2") (pintype "passive"))
      (node (ref "C4") (pin "2") (pinfunction "2_2") (pintype "passive"))
      (node (ref "L1") (pin "2") (pinfunction "2_2") (pintype "passive"))
      (node (ref "U2") (pin "3") (pinfunction "3.3V_3") (pintype "passive"))
    )
    (net (code "69") (name "Net-(U4-BOOT0)") (class "Default")
      (node (ref "R10") (pin "2") (pinfunction "2_2") (pintype "passive"))
      (node (ref "U4") (pin "94") (pinfunction "BOOT0_94") (pintype "passive"))
    )
    (net (code "70") (name "Net-(U4-PC14)") (class "Default")
      (node (ref "C5") (pin "2") (pinfunction "2_2") (pintype "passive"))
      (node (ref "U4") (pin "8") (pinfunction "PC14_8") (pintype "passive"))
      (node (ref "U5") (pin "1") (pinfunction "1_1") (pintype "passive"))
    )
    (net (code "71") (name "Net-(U4-PC15)") (class "Default")
      (node (ref "C6") (pin "2") (pinfunction "2_2") (pintype "passive"))
      (node (ref "U4") (pin "9") (pinfunction "PC15_9") (pintype "passive"))
      (node (ref "U5") (pin "2") (pinfunction "2_2") (pintype "passive"))
    )
    (net (code "72") (name "Net-(U4-PH0)") (class "Default")
      (node (ref "C7") (pin "2") (pinfunction "2_2") (pintype "passive"))
      (node (ref "U4") (pin "12") (pinfunction "PH0_12") (pintype "passive"))
      (node (ref "X1") (pin "3") (pinfunction "OSC2_3") (pintype "passive"))
    )
    (net (code "73") (name "Net-(U4-PH1)") (class "Default")
      (node (ref "C9") (pin "1") (pinfunction "1_1") (pintype "passive"))
      (node (ref "U4") (pin "13") (pinfunction "PH1_13") (pintype "passive"))
      (node (ref "X1") (pin "1") (pinfunction "OSC1_1") (pintype "passive"))
    )
    (net (code "74") (name "Net-(U4-VBAT)") (class "Default")
      (node (ref "BAT1") (pin "1") (pinfunction "1_1") (pintype "passive"))
      (node (ref "U4") (pin "6") (pinfunction "VBAT_6") (pintype "passive"))
    )
    (net (code "75") (name "Net-(U4-VCAP_1)") (class "Default")
      (node (ref "C14") (pin "2") (pinfunction "2_2") (pintype "passive"))
      (node (ref "U4") (pin "49") (pinfunction "VCAP_1_49") (pintype "passive"))
    )
    (net (code "76") (name "Net-(U4-VCAP_2)") (class "Default")
      (node (ref "C10") (pin "2") (pinfunction "2_2") (pintype "passive"))
      (node (ref "U4") (pin "73") (pinfunction "VCAP_2_73") (pintype "passive"))
    )
    (net (code "77") (name "Net-(U8-DN)") (class "Default")
      (node (ref "P2") (pin "1") (pinfunction "1_1") (pintype "passive"))
      (node (ref "U8") (pin "10") (pinfunction "DN_10") (pintype "passive"))
    )
    (net (code "78") (name "Net-(U8-DP)") (class "Default")
      (node (ref "P2") (pin "2") (pinfunction "2_2") (pintype "passive"))
      (node (ref "U8") (pin "9") (pinfunction "DP_9") (pintype "passive"))
    )
    (net (code "79") (name "Net-(U8-USB-V)") (class "Default")
      (node (ref "P2") (pin "4") (pinfunction "4_4") (pintype "passive"))
      (node (ref "U8") (pin "7") (pinfunction "USB-V_7") (pintype "passive"))
    )
    (net (code "80") (name "RFGND") (class "Default")
      (node (ref "C3") (pin "1") (pinfunction "1_1") (pintype "passive"))
      (node (ref "C4") (pin "1") (pinfunction "1_1") (pintype "passive"))
      (node (ref "R1") (pin "2") (pinfunction "2_2") (pintype "passive"))
      (node (ref "U2") (pin "1") (pinfunction "GND_1") (pintype "passive"))
      (node (ref "U2") (pin "16") (pinfunction "GND_16") (pintype "passive"))
      (node (ref "U2") (pin "2") (pinfunction "GND_2") (pintype "passive"))
      (node (ref "U2") (pin "9") (pinfunction "GND_9") (pintype "passive"))
    )
    (net (code "81") (name "VCC_2V8") (class "Default")
      (node (ref "EC2") (pin "1") (pinfunction "1_1") (pintype "passive"))
      (node (ref "J3") (pin "15") (pinfunction "15_15") (pintype "input"))
      (node (ref "U3") (pin "2") (pinfunction "Vout_2") (pintype "passive"))
    )
    (net (code "82") (name "VCC_3V3") (class "Default")
      (node (ref "C1") (pin "2") (pinfunction "2_2") (pintype "passive"))
      (node (ref "C15") (pin "2") (pinfunction "2_2") (pintype "passive"))
      (node (ref "C17") (pin "2") (pinfunction "2_2") (pintype "passive"))
      (node (ref "C18") (pin "2") (pinfunction "2_2") (pintype "passive"))
      (node (ref "C19") (pin "2") (pinfunction "2_2") (pintype "passive"))
      (node (ref "C2") (pin "2") (pinfunction "2_2") (pintype "passive"))
      (node (ref "C20") (pin "2") (pinfunction "2_2") (pintype "passive"))
      (node (ref "C21") (pin "2") (pinfunction "2_2") (pintype "passive"))
      (node (ref "C22") (pin "2") (pinfunction "2_2") (pintype "passive"))
      (node (ref "C23") (pin "2") (pinfunction "2_2") (pintype "passive"))
      (node (ref "C24") (pin "2") (pinfunction "2_2") (pintype "passive"))
      (node (ref "H1") (pin "1") (pinfunction "1_1") (pintype "passive"))
      (node (ref "J1") (pin "2") (pinfunction "2_2") (pintype "passive"))
      (node (ref "L1") (pin "1") (pinfunction "1_1") (pintype "passive"))
      (node (ref "P1") (pin "1") (pinfunction "1_1") (pintype "passive"))
      (node (ref "Q1") (pin "2") (pinfunction "S_2") (pintype "passive"))
      (node (ref "R11") (pin "2") (pinfunction "2_2") (pintype "passive"))
      (node (ref "R12") (pin "1") (pinfunction "1_1") (pintype "passive"))
      (node (ref "R14") (pin "2") (pinfunction "2_2") (pintype "passive"))
      (node (ref "R15") (pin "2") (pinfunction "2_2") (pintype "passive"))
      (node (ref "R16") (pin "2") (pinfunction "2_2") (pintype "passive"))
      (node (ref "R18") (pin "2") (pinfunction "2_2") (pintype "passive"))
      (node (ref "R19") (pin "2") (pinfunction "2_2") (pintype "passive"))
      (node (ref "R2") (pin "2") (pinfunction "2_2") (pintype "passive"))
      (node (ref "R20") (pin "1") (pinfunction "1_1") (pintype "passive"))
      (node (ref "R3") (pin "2") (pinfunction "2_2") (pintype "passive"))
      (node (ref "R4") (pin "2") (pinfunction "2_2") (pintype "passive"))
      (node (ref "R5") (pin "1") (pinfunction "1_1") (pintype "passive"))
      (node (ref "R6") (pin "2") (pinfunction "2_2") (pintype "passive"))
      (node (ref "R7") (pin "2") (pinfunction "2_2") (pintype "passive"))
      (node (ref "R8") (pin "2") (pinfunction "2_2") (pintype "passive"))
      (node (ref "R9") (pin "2") (pinfunction "2_2") (pintype "passive"))
      (node (ref "TF1") (pin "4") (pinfunction "VDD_4") (pintype "passive"))
      (node (ref "U1") (pin "8") (pinfunction "VCC_8") (pintype "passive"))
      (node (ref "U4") (pin "100") (pinfunction "VDD_100") (pintype "passive"))
      (node (ref "U4") (pin "11") (pinfunction "VDD_11") (pintype "passive"))
      (node (ref "U4") (pin "19") (pinfunction "VDD_19") (pintype "passive"))
      (node (ref "U4") (pin "22") (pinfunction "VDDA_22") (pintype "passive"))
      (node (ref "U4") (pin "28") (pinfunction "VDD_28") (pintype "passive"))
      (node (ref "U4") (pin "50") (pinfunction "VDD_50") (pintype "passive"))
      (node (ref "U4") (pin "75") (pinfunction "VDD_75") (pintype "passive"))
      (node (ref "U7") (pin "1") (pinfunction "VCC_1") (pintype "passive"))
    )
    (net (code "83") (name "unconnected-(J1-Pad15)") (class "Default")
      (node (ref "J1") (pin "15") (pinfunction "15_15") (pintype "passive"))
    )
    (net (code "84") (name "unconnected-(J3-Pad5)") (class "Default")
      (node (ref "J3") (pin "5") (pintype "passive+no_connect"))
    )
    (net (code "85") (name "unconnected-(SW1-Pad3)") (class "Default")
      (node (ref "SW1") (pin "3") (pinfunction "3_3") (pintype "passive"))
    )
    (net (code "86") (name "unconnected-(SW2-Pad3)") (class "Default")
      (node (ref "SW2") (pin "3") (pinfunction "3_3") (pintype "passive"))
    )
    (net (code "87") (name "unconnected-(SW3-Pad3)") (class "Default")
      (node (ref "SW3") (pin "3") (pinfunction "3_3") (pintype "passive"))
    )
    (net (code "88") (name "unconnected-(SW4-Pad3)") (class "Default")
      (node (ref "SW4") (pin "3") (pinfunction "3_3") (pintype "passive"))
    )
    (net (code "89") (name "unconnected-(U2-DIO2-Pad7)") (class "Default")
      (node (ref "U2") (pin "7") (pinfunction "DIO2_7") (pintype "passive"))
    )
    (net (code "90") (name "unconnected-(U2-DIO3-Pad8)") (class "Default")
      (node (ref "U2") (pin "8") (pinfunction "DIO3_8") (pintype "passive"))
    )
    (net (code "91") (name "unconnected-(U2-DIO4-Pad10)") (class "Default")
      (node (ref "U2") (pin "10") (pinfunction "DIO4_10") (pintype "passive"))
    )
    (net (code "92") (name "unconnected-(U2-DIO5-Pad11)") (class "Default")
      (node (ref "U2") (pin "11") (pinfunction "DIO5_11") (pintype "passive"))
    )
    (net (code "93") (name "unconnected-(U4-PB2-Pad37)") (class "Default")
      (node (ref "U4") (pin "37") (pinfunction "PB2_37") (pintype "passive"))
    )
    (net (code "94") (name "unconnected-(U4-PB3-Pad89)") (class "Default")
      (node (ref "U4") (pin "89") (pinfunction "PB3_89") (pintype "passive"))
    )
    (net (code "95") (name "unconnected-(U4-PB4-Pad90)") (class "Default")
      (node (ref "U4") (pin "90") (pinfunction "PB4_90") (pintype "passive"))
    )
    (net (code "96") (name "unconnected-(U4-PB5-Pad91)") (class "Default")
      (node (ref "U4") (pin "91") (pinfunction "PB5_91") (pintype "passive"))
    )
    (net (code "97") (name "unconnected-(U4-PB6-Pad92)") (class "Default")
      (node (ref "U4") (pin "92") (pinfunction "PB6_92") (pintype "passive"))
    )
    (net (code "98") (name "unconnected-(U4-PB7-Pad93)") (class "Default")
      (node (ref "U4") (pin "93") (pinfunction "PB7_93") (pintype "passive"))
    )
    (net (code "99") (name "unconnected-(U4-PB8-Pad95)") (class "Default")
      (node (ref "U4") (pin "95") (pinfunction "PB8_95") (pintype "passive"))
    )
    (net (code "100") (name "unconnected-(U4-PB9-Pad96)") (class "Default")
      (node (ref "U4") (pin "96") (pinfunction "PB9_96") (pintype "passive"))
    )
    (net (code "101") (name "unconnected-(U4-PC0-Pad15)") (class "Default")
      (node (ref "U4") (pin "15") (pinfunction "PC0_15") (pintype "passive"))
    )
    (net (code "102") (name "unconnected-(U4-PC1-Pad16)") (class "Default")
      (node (ref "U4") (pin "16") (pinfunction "PC1_16") (pintype "passive"))
    )
    (net (code "103") (name "unconnected-(U4-PC2-Pad17)") (class "Default")
      (node (ref "U4") (pin "17") (pinfunction "PC2_17") (pintype "passive"))
    )
    (net (code "104") (name "unconnected-(U4-PC3-Pad18)") (class "Default")
      (node (ref "U4") (pin "18") (pinfunction "PC3_18") (pintype "passive"))
    )
    (net (code "105") (name "unconnected-(U4-PC4-Pad33)") (class "Default")
      (node (ref "U4") (pin "33") (pinfunction "PC4_33") (pintype "passive"))
    )
    (net (code "106") (name "unconnected-(U4-PC5-Pad34)") (class "Default")
      (node (ref "U4") (pin "34") (pinfunction "PC5_34") (pintype "passive"))
    )
    (net (code "107") (name "unconnected-(U4-PC13-Pad7)") (class "Default")
      (node (ref "U4") (pin "7") (pinfunction "PC13_7") (pintype "passive"))
    )
    (net (code "108") (name "unconnected-(U4-PE0-Pad97)") (class "Default")
      (node (ref "U4") (pin "97") (pinfunction "PE0_97") (pintype "passive"))
    )
    (net (code "109") (name "unconnected-(U4-PE1-Pad98)") (class "Default")
      (node (ref "U4") (pin "98") (pinfunction "PE1_98") (pintype "passive"))
    )
    (net (code "110") (name "unconnected-(U4-PE2-Pad1)") (class "Default")
      (node (ref "U4") (pin "1") (pinfunction "PE2_1") (pintype "passive"))
    )
    (net (code "111") (name "unconnected-(U4-PE3-Pad2)") (class "Default")
      (node (ref "U4") (pin "2") (pinfunction "PE3_2") (pintype "passive"))
    )
    (net (code "112") (name "unconnected-(U4-PE4-Pad3)") (class "Default")
      (node (ref "U4") (pin "3") (pinfunction "PE4_3") (pintype "passive"))
    )
    (net (code "113") (name "unconnected-(U4-PE5-Pad4)") (class "Default")
      (node (ref "U4") (pin "4") (pinfunction "PE5_4") (pintype "passive"))
    )
    (net (code "114") (name "unconnected-(U4-PE11-Pad42)") (class "Default")
      (node (ref "U4") (pin "42") (pinfunction "PE11_42") (pintype "passive"))
    )
    (net (code "115") (name "unconnected-(U4-PE12-Pad43)") (class "Default")
      (node (ref "U4") (pin "43") (pinfunction "PE12_43") (pintype "passive"))
    )
    (net (code "116") (name "unconnected-(U4-PE13-Pad44)") (class "Default")
      (node (ref "U4") (pin "44") (pinfunction "PE13_44") (pintype "passive"))
    )
    (net (code "117") (name "unconnected-(U4-PE15-Pad46)") (class "Default")
      (node (ref "U4") (pin "46") (pinfunction "PE15_46") (pintype "passive"))
    )
    (net (code "118") (name "unconnected-(U4-VREF+-Pad21)") (class "Default")
      (node (ref "U4") (pin "21") (pinfunction "VREF+_21") (pintype "passive"))
    )
    (net (code "119") (name "unconnected-(U8-BAT-Pad6)") (class "Default")
      (node (ref "U8") (pin "6") (pinfunction "BAT_6") (pintype "passive"))
    )
    (net (code "120") (name "unconnected-(U8-BOOT-Pad12)") (class "Default")
      (node (ref "U8") (pin "12") (pinfunction "BOOT_12") (pintype "passive"))
    )
    (net (code "121") (name "unconnected-(U8-LED-Pad11)") (class "Default")
      (node (ref "U8") (pin "11") (pinfunction "LED_11") (pintype "passive"))
    )
  )
)
